# pca20020_sheet9_interface.net
KiCad netlist of a schematic drawn in Altium Designer
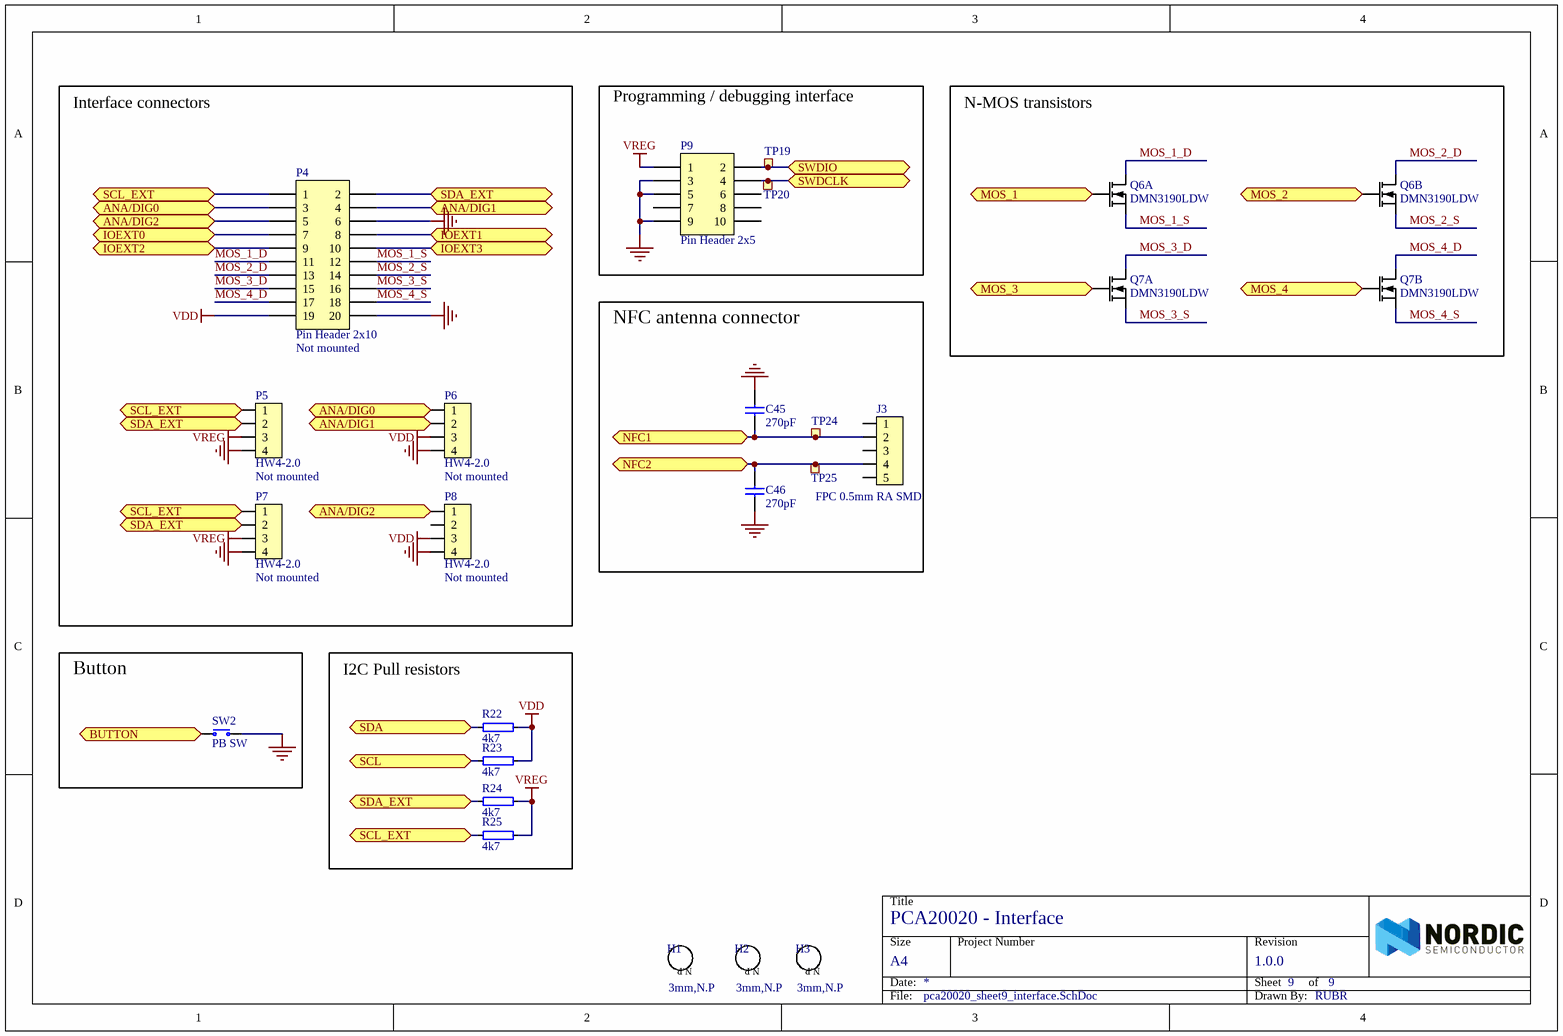
[diagram p0: pca20020_sheet9_interface.SchDoc]

(export (version "E")
  (design (tool "Eeschema 10.0.6"))
  (components
    (comp (ref "C45")
      (value "270pF")
      (footprint "CAPC1005X04L")
      (description "Capacitor, NP0, ±5%")
      (fields (field (name "PART NUMBER") "C0402-270p") (field (name "PUBLISHER") "Nordic Semiconductor"))
      (libsource (lib "Nordic Passive DB") (part "CAP"))
    )
    (comp (ref "C46")
      (value "270pF")
      (footprint "CAPC1005X04L")
      (description "Capacitor, NP0, ±5%")
      (fields (field (name "PART NUMBER") "C0402-270p") (field (name "PUBLISHER") "Nordic Semiconductor"))
      (libsource (lib "Nordic Passive DB") (part "CAP"))
    )
    (comp (ref "H1")
      (value "3mm,N.P")
      (footprint "HOLE_NP_3MM")
      (description "Regular Non-Plated, 3mm hole")
      (fields
        (field (name "PART NUMBER") "Hole_3MM_NP")
        (field (name "MANUFACTURER") "Nordic Semiconductor")
        (field (name "PUBLISHER") "Nordic Semiconductor")
      )
      (libsource (lib "Nordic Passive DB") (part "HOLE_NP"))
    )
    (comp (ref "H2")
      (value "3mm,N.P")
      (footprint "HOLE_NP_3MM")
      (description "Regular Non-Plated, 3mm hole")
      (fields
        (field (name "PART NUMBER") "Hole_3MM_NP")
        (field (name "MANUFACTURER") "Nordic Semiconductor")
        (field (name "PUBLISHER") "Nordic Semiconductor")
      )
      (libsource (lib "Nordic Passive DB") (part "HOLE_NP"))
    )
    (comp (ref "H3")
      (value "3mm,N.P")
      (footprint "HOLE_NP_3MM")
      (description "Regular Non-Plated, 3mm hole")
      (fields
        (field (name "PART NUMBER") "Hole_3MM_NP")
        (field (name "MANUFACTURER") "Nordic Semiconductor")
        (field (name "PUBLISHER") "Nordic Semiconductor")
      )
      (libsource (lib "Nordic Passive DB") (part "HOLE_NP"))
    )
    (comp (ref "J3")
      (value "FPC 0.5mm RA SMD")
      (footprint "FPC_05P-0.5mm-RA-SMD")
      (description "0.5mm FPC, 5P,Right Angle SMT,Double Contact,H=1.2mm,White, Tin plated")
      (fields
        (field (name "PART NUMBER") "FPC_05P-0.5mm-RA-SMD")
        (field (name "MANUFACTURER") "W-CON")
        (field (name "PUBLISHER") "Nordic Semiconductor")
      )
      (libsource (lib "Nordic Passive DB") (part "CONN-5"))
    )
    (comp (ref "P4")
      (value "Pin Header 2x10")
      (footprint "HDR_2x10-NC")
      (description "Pin Header 2x10, 2.54mm (100mil)")
      (fields
        (field (name "PART NUMBER") "Pin Header 2x10, N.C.")
        (field (name "ASSEMBLY") "Not mounted")
        (field (name "PUBLISHER") "Nordic Semiconductor")
      )
      (libsource (lib "Nordic Passive DB") (part "CONN-2x10"))
    )
    (comp (ref "P5")
      (value "HW4-2.0")
      (footprint "TAIFENG_HW4-2.0-NC")
      (description "4 pin, Grove DIP connector")
      (fields
        (field (name "PART NUMBER") "Taifeng_HW4-2.0, N.C.")
        (field (name "ASSEMBLY") "Not mounted")
        (field (name "MANUFACTURER") "Taifeng")
        (field (name "PUBLISHER") "Nordic Semiconductor")
      )
      (libsource (lib "Nordic Passive DB") (part "CONN-4"))
    )
    (comp (ref "P6")
      (value "HW4-2.0")
      (footprint "TAIFENG_HW4-2.0-NC")
      (description "4 pin, Grove DIP connector")
      (fields
        (field (name "PART NUMBER") "Taifeng_HW4-2.0, N.C.")
        (field (name "ASSEMBLY") "Not mounted")
        (field (name "MANUFACTURER") "Taifeng")
        (field (name "PUBLISHER") "Nordic Semiconductor")
      )
      (libsource (lib "Nordic Passive DB") (part "CONN-4"))
    )
    (comp (ref "P7")
      (value "HW4-2.0")
      (footprint "TAIFENG_HW4-2.0-NC")
      (description "4 pin, Grove DIP connector")
      (fields
        (field (name "PART NUMBER") "Taifeng_HW4-2.0, N.C.")
        (field (name "ASSEMBLY") "Not mounted")
        (field (name "MANUFACTURER") "Taifeng")
        (field (name "PUBLISHER") "Nordic Semiconductor")
      )
      (libsource (lib "Nordic Passive DB") (part "CONN-4"))
    )
    (comp (ref "P8")
      (value "HW4-2.0")
      (footprint "TAIFENG_HW4-2.0-NC")
      (description "4 pin, Grove DIP connector")
      (fields
        (field (name "PART NUMBER") "Taifeng_HW4-2.0, N.C.")
        (field (name "ASSEMBLY") "Not mounted")
        (field (name "MANUFACTURER") "Taifeng")
        (field (name "PUBLISHER") "Nordic Semiconductor")
      )
      (libsource (lib "Nordic Passive DB") (part "CONN-4"))
    )
    (comp (ref "P9")
      (value "Pin Header 2x5")
      (footprint "HDR_2x5-SMD-1.27mm-ANG")
      (description "Pin Header 2x5, 1.27mm (50mil)")
      (fields
        (field (name "PART NUMBER") "Pin Header 2x5 SMD, 1.27mm, Angled")
        (field (name "MANUFACTURER") "Samtec")
        (field (name "PUBLISHER") "Nordic Semiconductor")
      )
      (libsource (lib "Nordic Passive DB") (part "CONN-2x5"))
    )
    (comp (ref "Q6")
      (value "DMN3190LDW")
      (footprint "SOT-363")
      (description "Dual N Ch MOFET, 1A, 190mOhm, 320mW")
      (fields
        (field (name "MANUFACTURER") "Diodes Incorporated")
        (field (name "PUBLISHER") "Nordic Semiconductor")
      )
      (libsource (lib "Nordic Discrete DB") (part "T{colon}FET-N-DUAL"))
    )
    (comp (ref "Q7")
      (value "DMN3190LDW")
      (footprint "SOT-363")
      (description "Dual N Ch MOFET, 1A, 190mOhm, 320mW")
      (fields
        (field (name "MANUFACTURER") "Diodes Incorporated")
        (field (name "PUBLISHER") "Nordic Semiconductor")
      )
      (libsource (lib "Nordic Discrete DB") (part "T{colon}FET-N-DUAL"))
    )
    (comp (ref "R22")
      (value "4k7")
      (footprint "RESC1005X04L")
      (description "Resistor, ±1%, 0.063W")
      (fields (field (name "PART NUMBER") "R0402-4k7") (field (name "PUBLISHER") "Nordic Semiconductor"))
      (libsource (lib "Nordic Passive DB") (part "RES_1"))
    )
    (comp (ref "R23")
      (value "4k7")
      (footprint "RESC1005X04L")
      (description "Resistor, ±1%, 0.063W")
      (fields (field (name "PART NUMBER") "R0402-4k7") (field (name "PUBLISHER") "Nordic Semiconductor"))
      (libsource (lib "Nordic Passive DB") (part "RES_1"))
    )
    (comp (ref "R24")
      (value "4k7")
      (footprint "RESC1005X04L")
      (description "Resistor, ±1%, 0.063W")
      (fields (field (name "PART NUMBER") "R0402-4k7") (field (name "PUBLISHER") "Nordic Semiconductor"))
      (libsource (lib "Nordic Passive DB") (part "RES_1"))
    )
    (comp (ref "R25")
      (value "4k7")
      (footprint "RESC1005X04L")
      (description "Resistor, ±1%, 0.063W")
      (fields (field (name "PART NUMBER") "R0402-4k7") (field (name "PUBLISHER") "Nordic Semiconductor"))
      (libsource (lib "Nordic Passive DB") (part "RES_1"))
    )
    (comp (ref "SW2")
      (value "PB SW")
      (footprint "Switch-PB-6.2x6.3mm-SMD")
      (description "Tactile Switch, SPNO, SMD, 160gf, 6.2x6.3x2.5mm")
      (fields
        (field (name "PART NUMBER") "Switch-PB-6.2x6.3mm-SMD")
        (field (name "MANUFACTURER") "Dailywell")
        (field (name "PUBLISHER") "Nordic Semiconductor")
      )
      (libsource (lib "Nordic Discrete DB") (part "SW-PB"))
    )
    (comp (ref "TP19")
      (value "Ø1.5mm,SMD")
      (footprint "TP_SMD_Ø1.5mm")
      (description "1.0mm circular SMD testpad")
      (fields
        (field (name "PART NUMBER") "TP_SMD_Ø1.5MM")
        (field (name "MANUFACTURER") "Nordic Semiconductor")
        (field (name "PUBLISHER") "Nordic Semiconductor")
      )
      (libsource (lib "") (part "TESTPAD_1"))
    )
    (comp (ref "TP20")
      (value "Ø1.5mm,SMD")
      (footprint "TP_SMD_Ø1.5mm")
      (description "1.0mm circular SMD testpad")
      (fields
        (field (name "PART NUMBER") "TP_SMD_Ø1.5MM")
        (field (name "MANUFACTURER") "Nordic Semiconductor")
        (field (name "PUBLISHER") "Nordic Semiconductor")
      )
      (libsource (lib "Nordic Passive DB") (part "TESTPAD"))
    )
    (comp (ref "TP24")
      (value "Ø1.5mm,SMD")
      (footprint "TP_SMD_Ø1.0mm")
      (description "1.0mm circular SMD testpad")
      (fields
        (field (name "PART NUMBER") "TP_SMD_Ø1.5MM")
        (field (name "MANUFACTURER") "Nordic Semiconductor")
        (field (name "PUBLISHER") "Nordic Semiconductor")
      )
      (libsource (lib "") (part "TESTPAD_1"))
    )
    (comp (ref "TP25")
      (value "Ø1.5mm,SMD")
      (footprint "TP_SMD_Ø1.0mm")
      (description "1.0mm circular SMD testpad")
      (fields
        (field (name "PART NUMBER") "TP_SMD_Ø1.5MM")
        (field (name "MANUFACTURER") "Nordic Semiconductor")
        (field (name "PUBLISHER") "Nordic Semiconductor")
      )
      (libsource (lib "Nordic Passive DB") (part "TESTPAD"))
    )
  )
  (nets
    (net (code "1") (name "/ANA{slash}DIG0") (class "Default")
      (node (ref "P4") (pin "3") (pinfunction "3_3") (pintype "passive"))
      (node (ref "P6") (pin "1") (pinfunction "1_1") (pintype "passive"))
    )
    (net (code "2") (name "/ANA{slash}DIG1") (class "Default")
      (node (ref "P4") (pin "4") (pinfunction "4_4") (pintype "passive"))
      (node (ref "P6") (pin "2") (pinfunction "2_2") (pintype "passive"))
    )
    (net (code "3") (name "/ANA{slash}DIG2") (class "Default")
      (node (ref "P4") (pin "5") (pinfunction "5_5") (pintype "passive"))
      (node (ref "P8") (pin "1") (pinfunction "1_1") (pintype "passive"))
    )
    (net (code "4") (name "/BUTTON") (class "Default")
      (node (ref "SW2") (pin "2") (pinfunction "COM_2") (pintype "passive"))
    )
    (net (code "5") (name "/IOEXT0") (class "Default")
      (node (ref "P4") (pin "7") (pinfunction "7_7") (pintype "passive"))
    )
    (net (code "6") (name "/IOEXT1") (class "Default")
      (node (ref "P4") (pin "8") (pinfunction "8_8") (pintype "passive"))
    )
    (net (code "7") (name "/IOEXT2") (class "Default")
      (node (ref "P4") (pin "9") (pinfunction "9_9") (pintype "passive"))
    )
    (net (code "8") (name "/IOEXT3") (class "Default")
      (node (ref "P4") (pin "10") (pinfunction "10_10") (pintype "passive"))
    )
    (net (code "9") (name "/MOS_1") (class "Default")
      (node (ref "Q6") (pin "2") (pinfunction "G1_2") (pintype "passive"))
    )
    (net (code "10") (name "/MOS_1_D") (class "Default")
      (node (ref "P4") (pin "11") (pinfunction "11_11") (pintype "passive"))
      (node (ref "Q6") (pin "6") (pinfunction "D1_6") (pintype "passive"))
    )
    (net (code "11") (name "/MOS_1_S") (class "Default")
      (node (ref "P4") (pin "12") (pinfunction "12_12") (pintype "passive"))
      (node (ref "Q6") (pin "1") (pinfunction "S1_1") (pintype "passive"))
    )
    (net (code "12") (name "/MOS_2") (class "Default")
      (node (ref "Q6") (pin "5") (pinfunction "G2_5") (pintype "passive"))
    )
    (net (code "13") (name "/MOS_2_D") (class "Default")
      (node (ref "P4") (pin "13") (pinfunction "13_13") (pintype "passive"))
      (node (ref "Q6") (pin "3") (pinfunction "D2_3") (pintype "passive"))
    )
    (net (code "14") (name "/MOS_2_S") (class "Default")
      (node (ref "P4") (pin "14") (pinfunction "14_14") (pintype "passive"))
      (node (ref "Q6") (pin "4") (pinfunction "S2_4") (pintype "passive"))
    )
    (net (code "15") (name "/MOS_3") (class "Default")
      (node (ref "Q7") (pin "2") (pinfunction "G1_2") (pintype "passive"))
    )
    (net (code "16") (name "/MOS_3_D") (class "Default")
      (node (ref "P4") (pin "15") (pinfunction "15_15") (pintype "passive"))
      (node (ref "Q7") (pin "6") (pinfunction "D1_6") (pintype "passive"))
    )
    (net (code "17") (name "/MOS_3_S") (class "Default")
      (node (ref "P4") (pin "16") (pinfunction "16_16") (pintype "passive"))
      (node (ref "Q7") (pin "1") (pinfunction "S1_1") (pintype "passive"))
    )
    (net (code "18") (name "/MOS_4") (class "Default")
      (node (ref "Q7") (pin "5") (pinfunction "G2_5") (pintype "passive"))
    )
    (net (code "19") (name "/MOS_4_D") (class "Default")
      (node (ref "P4") (pin "17") (pinfunction "17_17") (pintype "passive"))
      (node (ref "Q7") (pin "3") (pinfunction "D2_3") (pintype "passive"))
    )
    (net (code "20") (name "/MOS_4_S") (class "Default")
      (node (ref "P4") (pin "18") (pinfunction "18_18") (pintype "passive"))
      (node (ref "Q7") (pin "4") (pinfunction "S2_4") (pintype "passive"))
    )
    (net (code "21") (name "/NFC1") (class "Default")
      (node (ref "C45") (pin "1") (pinfunction "1_1") (pintype "passive"))
      (node (ref "J3") (pin "2") (pinfunction "2_2") (pintype "passive"))
      (node (ref "TP24") (pin "1") (pinfunction "1_1") (pintype "passive"))
    )
    (net (code "22") (name "/NFC2") (class "Default")
      (node (ref "C46") (pin "2") (pinfunction "2_2") (pintype "passive"))
      (node (ref "J3") (pin "4") (pinfunction "4_4") (pintype "passive"))
      (node (ref "TP25") (pin "1") (pinfunction "1_1") (pintype "passive"))
    )
    (net (code "23") (name "/SCL") (class "Default")
      (node (ref "R23") (pin "2") (pinfunction "2_2") (pintype "passive"))
    )
    (net (code "24") (name "/SCL_EXT") (class "Default")
      (node (ref "P4") (pin "1") (pinfunction "1_1") (pintype "passive"))
      (node (ref "P5") (pin "1") (pinfunction "1_1") (pintype "passive"))
      (node (ref "P7") (pin "1") (pinfunction "1_1") (pintype "passive"))
      (node (ref "R25") (pin "2") (pinfunction "2_2") (pintype "passive"))
    )
    (net (code "25") (name "/SDA") (class "Default")
      (node (ref "R22") (pin "2") (pinfunction "2_2") (pintype "passive"))
    )
    (net (code "26") (name "/SDA_EXT") (class "Default")
      (node (ref "P4") (pin "2") (pinfunction "2_2") (pintype "passive"))
      (node (ref "P5") (pin "2") (pinfunction "2_2") (pintype "passive"))
      (node (ref "P7") (pin "2") (pinfunction "2_2") (pintype "passive"))
      (node (ref "R24") (pin "2") (pinfunction "2_2") (pintype "passive"))
    )
    (net (code "27") (name "/SWDCLK") (class "Default")
      (node (ref "P9") (pin "4") (pinfunction "4_4") (pintype "passive"))
      (node (ref "TP20") (pin "1") (pinfunction "1_1") (pintype "passive"))
    )
    (net (code "28") (name "/SWDIO") (class "Default")
      (node (ref "P9") (pin "2") (pinfunction "2_2") (pintype "passive"))
      (node (ref "TP19") (pin "1") (pinfunction "1_1") (pintype "passive"))
    )
    (net (code "29") (name "GND") (class "Default")
      (node (ref "C45") (pin "2") (pinfunction "2_2") (pintype "passive"))
      (node (ref "C46") (pin "1") (pinfunction "1_1") (pintype "passive"))
      (node (ref "P4") (pin "20") (pinfunction "20_20") (pintype "passive"))
      (node (ref "P4") (pin "6") (pinfunction "6_6") (pintype "passive"))
      (node (ref "P5") (pin "4") (pinfunction "4_4") (pintype "passive"))
      (node (ref "P6") (pin "4") (pinfunction "4_4") (pintype "passive"))
      (node (ref "P7") (pin "4") (pinfunction "4_4") (pintype "passive"))
      (node (ref "P8") (pin "4") (pinfunction "4_4") (pintype "passive"))
      (node (ref "P9") (pin "3") (pinfunction "3_3") (pintype "passive"))
      (node (ref "P9") (pin "5") (pinfunction "5_5") (pintype "passive"))
      (node (ref "P9") (pin "9") (pinfunction "9_9") (pintype "passive"))
      (node (ref "SW2") (pin "1") (pinfunction "N.O_1") (pintype "passive"))
    )
    (net (code "30") (name "VDD") (class "Default")
      (node (ref "P4") (pin "19") (pinfunction "19_19") (pintype "passive"))
      (node (ref "P6") (pin "3") (pinfunction "3_3") (pintype "passive"))
      (node (ref "P8") (pin "3") (pinfunction "3_3") (pintype "passive"))
      (node (ref "R22") (pin "1") (pinfunction "1_1") (pintype "passive"))
      (node (ref "R23") (pin "1") (pinfunction "1_1") (pintype "passive"))
    )
    (net (code "31") (name "VREG") (class "Default")
      (node (ref "P5") (pin "3") (pinfunction "3_3") (pintype "passive"))
      (node (ref "P7") (pin "3") (pinfunction "3_3") (pintype "passive"))
      (node (ref "P9") (pin "1") (pinfunction "1_1") (pintype "passive"))
      (node (ref "R24") (pin "1") (pinfunction "1_1") (pintype "passive"))
      (node (ref "R25") (pin "1") (pinfunction "1_1") (pintype "passive"))
    )
    (net (code "32") (name "unconnected-(J3-Pad1)") (class "Default")
      (node (ref "J3") (pin "1") (pinfunction "1_1") (pintype "passive"))
    )
    (net (code "33") (name "unconnected-(J3-Pad3)") (class "Default")
      (node (ref "J3") (pin "3") (pinfunction "3_3") (pintype "passive"))
    )
    (net (code "34") (name "unconnected-(J3-Pad5)") (class "Default")
      (node (ref "J3") (pin "5") (pinfunction "5_5") (pintype "passive"))
    )
    (net (code "35") (name "unconnected-(P8-Pad2)") (class "Default")
      (node (ref "P8") (pin "2") (pinfunction "2_2") (pintype "passive"))
    )
    (net (code "36") (name "unconnected-(P9-Pad6)") (class "Default")
      (node (ref "P9") (pin "6") (pinfunction "6_6") (pintype "passive"))
    )
    (net (code "37") (name "unconnected-(P9-Pad7)") (class "Default")
      (node (ref "P9") (pin "7") (pinfunction "7_7") (pintype "passive"))
    )
    (net (code "38") (name "unconnected-(P9-Pad8)") (class "Default")
      (node (ref "P9") (pin "8") (pinfunction "8_8") (pintype "passive"))
    )
    (net (code "39") (name "unconnected-(P9-Pad10)") (class "Default")
      (node (ref "P9") (pin "10") (pinfunction "10_10") (pintype "passive"))
    )
  )
)
